# Serial_Expansion.net
KiCad netlist of a schematic drawn in Altium Designer
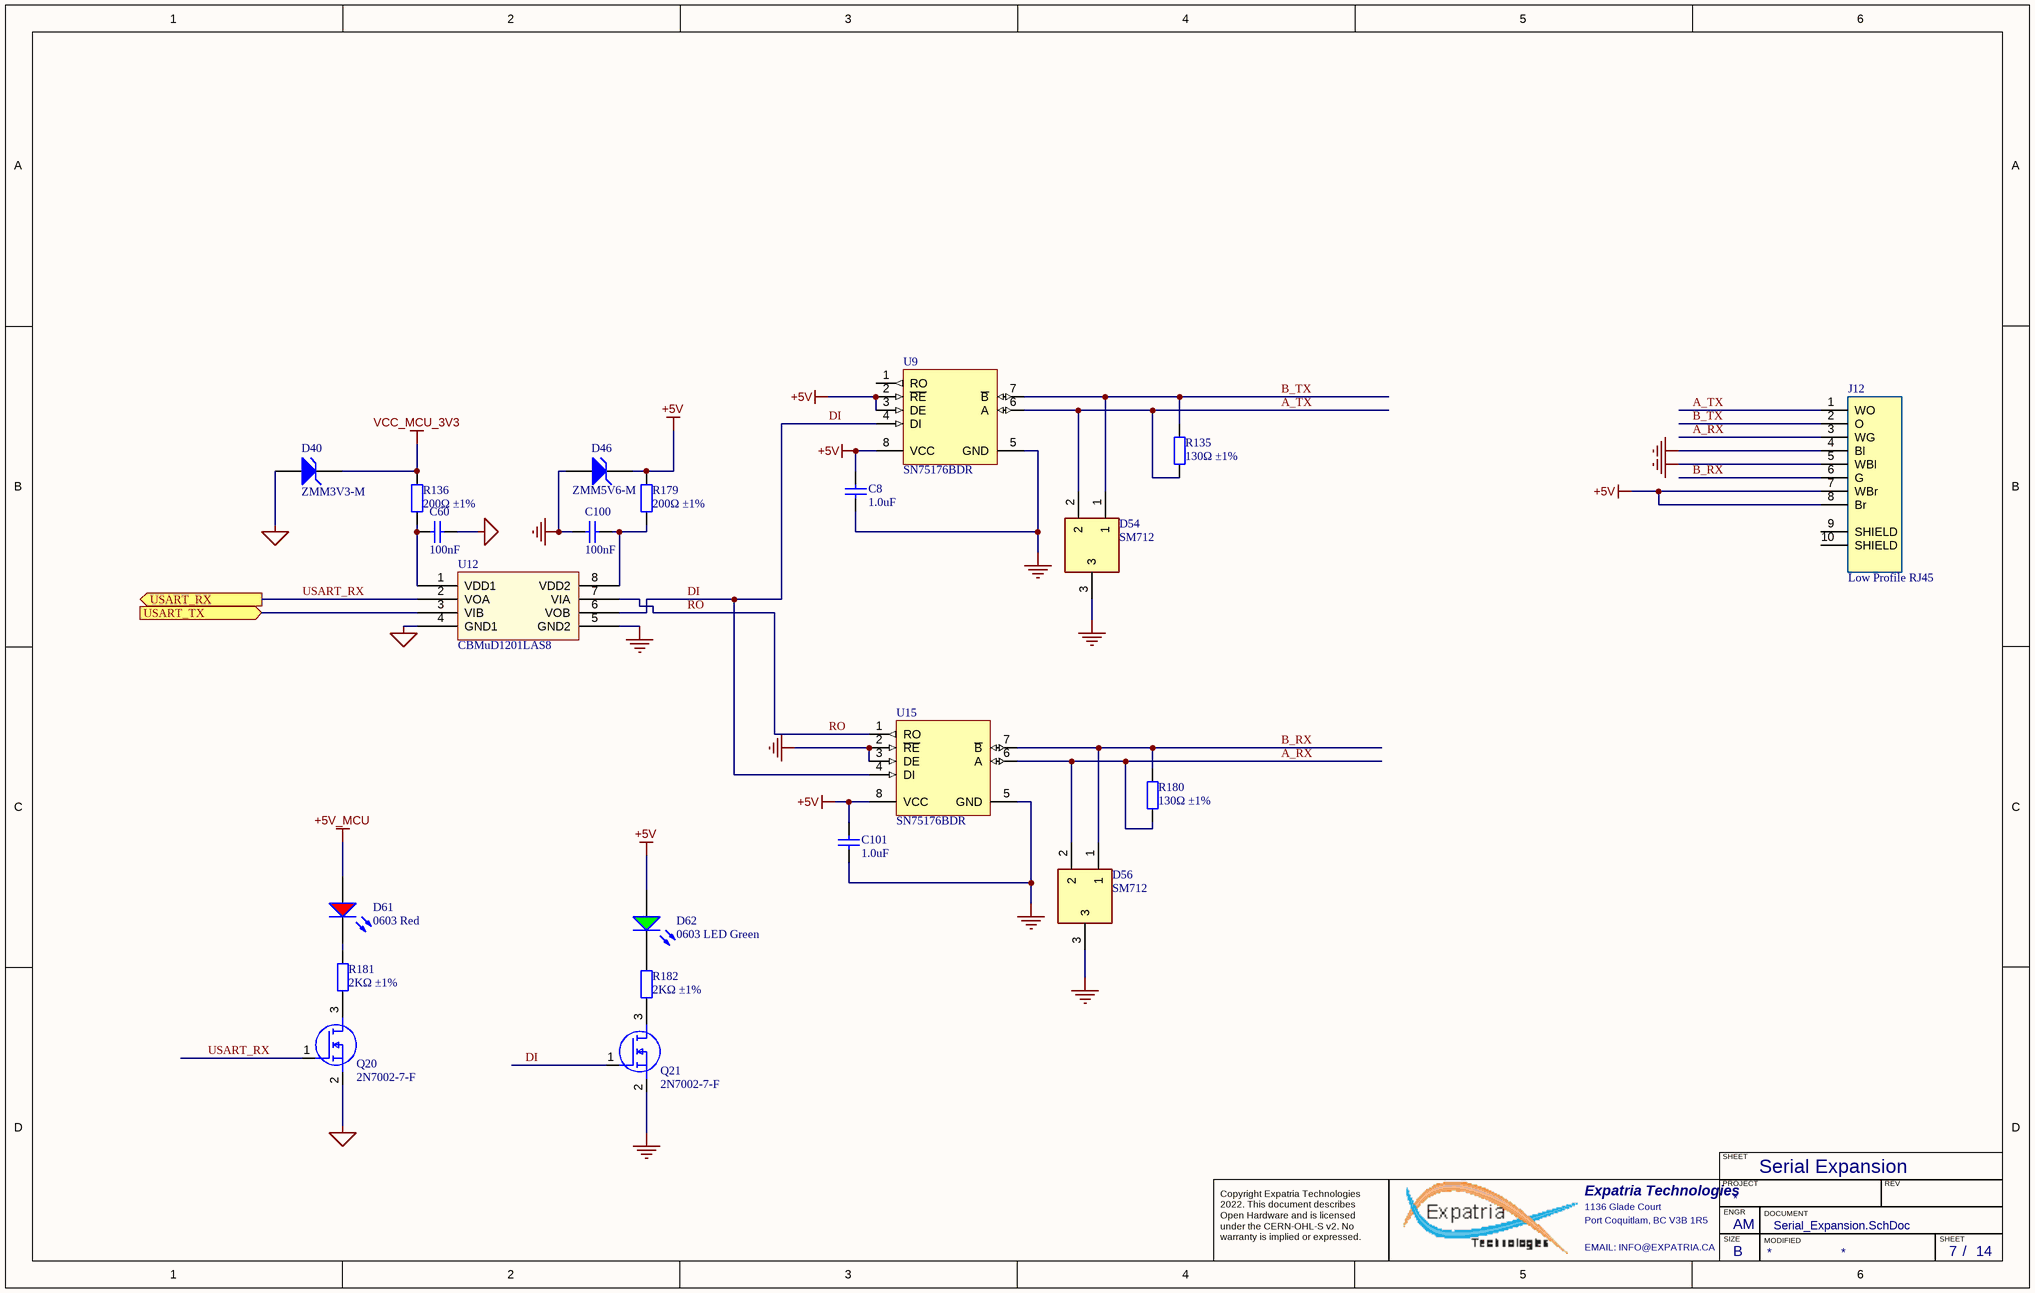
[diagram p0: Serial_Expansion.SchDoc]

(export (version "E")
  (design (tool "Eeschema 10.0.6"))
  (components
    (comp (ref "C8")
      (value "1.0uF")
      (footprint "0402_C")
      (description "Chip capacitor")
      (fields
        (field (name "MANUFACTURER") "Samsung Electro-Mechanics")
        (field (name "PARTNUMBER") "CL05A105KA5NQNC")
      )
      (libsource (lib "Cap") (part "0402 1.0uF (105) 10% 25V"))
    )
    (comp (ref "C60")
      (value "100nF")
      (footprint "0402_C")
      (description "16V 100nF X7R ±10% 0402 Multilayer Ceramic Capacitors MLCC - SMD/SMT ROHS")
      (fields (field (name "MANUFACTURER") "Samsung Electro-Mechanics") (field (name "TOLERANCE") "10%"))
      (libsource (lib "Sienci_Labs") (part "0402 100nF (104) 10% 16V"))
    )
    (comp (ref "C100")
      (value "100nF")
      (footprint "0402_C")
      (description "16V 100nF X7R ±10% 0402 Multilayer Ceramic Capacitors MLCC - SMD/SMT ROHS")
      (fields (field (name "MANUFACTURER") "Samsung Electro-Mechanics") (field (name "TOLERANCE") "10%"))
      (libsource (lib "Sienci_Labs") (part "0402 100nF (104) 10% 16V"))
    )
    (comp (ref "C101")
      (value "1.0uF")
      (footprint "0402_C")
      (description "Chip capacitor")
      (fields
        (field (name "MANUFACTURER") "Samsung Electro-Mechanics")
        (field (name "PARTNUMBER") "CL05A105KA5NQNC")
      )
      (libsource (lib "Cap") (part "0402 1.0uF (105) 10% 25V"))
    )
    (comp (ref "D40")
      (value "ZMM3V3-M")
      (footprint "LL-34")
      (description "Single 3.1V~3.5V 500mW 3.3V LL-34 Zener Diodes ROHS")
      (fields (field (name "MANUFACTURER") "ST(Semtech)"))
      (libsource (lib "Sienci_Labs") (part "LL-34 ZMM3V3-M"))
    )
    (comp (ref "D46")
      (value "ZMM5V6-M")
      (footprint "LL-34")
      (description "Single 5.2V~6V 500mW 5.6V LL-34 Zener Diodes ROHS")
      (fields (field (name "MANUFACTURER") "ST(Semtech)"))
      (libsource (lib "Sienci_Labs") (part "LL-34 ZMM5V6-M"))
    )
    (comp (ref "D54")
      (value "SM712")
      (footprint "SamacSys:SOT95P230X117-3N")
      (description "Bidirectional 12V (Max), 7V (Max) 7.5V / 13.3V 10V / 20V 12A(8/20us) SOT-23-3 TVS RoHS")
      (libsource (lib "*") (part "CDSOT23-SM712"))
    )
    (comp (ref "D56")
      (value "SM712")
      (footprint "SamacSys:SOT95P230X117-3N")
      (description "Bidirectional 12V (Max), 7V (Max) 7.5V / 13.3V 10V / 20V 12A(8/20us) SOT-23-3 TVS RoHS")
      (libsource (lib "*") (part "CDSOT23-SM712"))
    )
    (comp (ref "D61")
      (value "0603 Red")
      (footprint "0603_LED_S1")
      (fields
        (field (name "MANUFACTURER") "Everlight Elec")
        (field (name "MANUFACTURER PART NUMBER") "19-213SURC/S530-A3/TR8")
      )
      (libsource (lib "Sienci_Labs") (part "19-213SURC/S530-A3/TR8"))
    )
    (comp (ref "D62")
      (value "0603 LED Green")
      (footprint "0603_LED_S1")
      (fields
        (field (name "MANUFACTURER PART NUMBER") "19-217/GHC-YR1S2/3T")
        (field (name "MANUFACTURER") "Everlight Elec")
      )
      (libsource (lib "Sienci_Labs") (part "19-217/GHC-YR1S2/3T"))
    )
    (comp (ref "J12")
      (value "Low Profile RJ45")
      (footprint "RJ45-SMD_MJ88-B011-HLSV6-P")
      (description "Micro USB")
      (fields (field (name "MF") "Heling"))
      (libsource (lib "Universal_CNC_Breakout") (part "MJ88-B011-HLSV6-P"))
    )
    (comp (ref "Q20")
      (value "2N7002-7-F")
      (footprint "SOT-23(SOT-23-3)")
      (description "60V 115mA 7.5Ω@5V,50mA 370mW N Channel SOT-23 MOSFETs ROHS")
      (fields (field (name "MANUFACTURER") "Diodes Inc.") (field (name "MOUSER PART NUMBER") "621-2N7002-F"))
      (libsource (lib "Sienci_Labs") (part "2N7002-7-F"))
    )
    (comp (ref "Q21")
      (value "2N7002-7-F")
      (footprint "SOT-23(SOT-23-3)")
      (description "60V 115mA 7.5Ω@5V,50mA 370mW N Channel SOT-23 MOSFETs ROHS")
      (fields (field (name "MANUFACTURER") "Diodes Inc.") (field (name "MOUSER PART NUMBER") "621-2N7002-F"))
      (libsource (lib "Sienci_Labs") (part "2N7002-7-F"))
    )
    (comp (ref "R135")
      (value "130Ω ±1%")
      (footprint "0603_R")
      (description "Chip resistor")
      (fields (field (name "MANUFACTURER") "Uniroyal Elec") (field (name "PARTNUMBER") "0603WAF1300T5E"))
      (libsource (lib "RES") (part "0603 130R (1300) 1%"))
    )
    (comp (ref "R136")
      (value "200Ω ±1%")
      (footprint "0402_R")
      (description "Chip resistor")
      (fields
        (field (name "MANUFACTURER") "Uniroyal Elec")
        (field (name "MANUFACTURER PART NUMBER") "0402WGF2000TCE")
      )
      (libsource (lib "RES") (part "0402 200R (2000) 1%"))
    )
    (comp (ref "R179")
      (value "200Ω ±1%")
      (footprint "0402_R")
      (description "Chip resistor")
      (fields
        (field (name "MANUFACTURER") "Uniroyal Elec")
        (field (name "MANUFACTURER PART NUMBER") "0402WGF2000TCE")
      )
      (libsource (lib "RES") (part "0402 200R (2000) 1%"))
    )
    (comp (ref "R180")
      (value "130Ω ±1%")
      (footprint "0603_R")
      (description "Chip resistor")
      (fields (field (name "MANUFACTURER") "Uniroyal Elec") (field (name "PARTNUMBER") "0603WAF1300T5E"))
      (libsource (lib "RES") (part "0603 130R (1300) 1%"))
    )
    (comp (ref "R181")
      (value "2KΩ ±1%")
      (footprint "0402_R")
      (description "Chip resistor")
      (fields
        (field (name "MANUFACTURER") "Uniroyal Elec")
        (field (name "MANUFACTURER PART NUMBER") "0402WGF2001TCE")
      )
      (libsource (lib "RES") (part "0402 2K (2001) 1%"))
    )
    (comp (ref "R182")
      (value "2KΩ ±1%")
      (footprint "0402_R")
      (description "Chip resistor")
      (fields
        (field (name "MANUFACTURER") "Uniroyal Elec")
        (field (name "MANUFACTURER PART NUMBER") "0402WGF2001TCE")
      )
      (libsource (lib "RES") (part "0402 2K (2001) 1%"))
    )
    (comp (ref "U9")
      (value "SN75176BDR")
      (footprint "Miscellaneous Devices LC:SOIC-8_150mil")
      (description "RS-485/RS-422")
      (libsource (lib "IC") (part "SN75176BDR_[C7063]"))
    )
    (comp (ref "U12")
      (value "CBMuD1201LAS8")
      (footprint "SOIC-8_150mil")
      (description "Dual Channel Isolator")
      (fields (field (name "MANUFACTURER") "Corebai Microelectronics"))
      (libsource (lib "Sienci_Labs") (part "CBMuD1201LAS8"))
    )
    (comp (ref "U15")
      (value "SN75176BDR")
      (footprint "Miscellaneous Devices LC:SOIC-8_150mil")
      (description "RS-485/RS-422")
      (libsource (lib "IC") (part "SN75176BDR_[C7063]"))
    )
  )
  (nets
    (net (code "1") (name "+5V") (class "Default")
      (node (ref "C101") (pin "2") (pinfunction "2_2") (pintype "passive"))
      (node (ref "C8") (pin "2") (pinfunction "2_2") (pintype "passive"))
      (node (ref "D46") (pin "2") (pinfunction "K_2") (pintype "passive"))
      (node (ref "D62") (pin "A") (pinfunction "A_A") (pintype "passive"))
      (node (ref "J12") (pin "7") (pinfunction "WBr_7") (pintype "passive"))
      (node (ref "J12") (pin "8") (pinfunction "Br_8") (pintype "passive"))
      (node (ref "R179") (pin "2") (pinfunction "2_2") (pintype "passive"))
      (node (ref "U15") (pin "8") (pinfunction "VCC_8") (pintype "power_in"))
      (node (ref "U9") (pin "2") (pinfunction "~{RE}_2") (pintype "input"))
      (node (ref "U9") (pin "3") (pinfunction "DE_3") (pintype "input"))
      (node (ref "U9") (pin "8") (pinfunction "VCC_8") (pintype "power_in"))
    )
    (net (code "2") (name "+5V_MCU") (class "Default")
      (node (ref "D61") (pin "A") (pinfunction "A_A") (pintype "passive"))
    )
    (net (code "3") (name "/A_RX") (class "Default")
      (node (ref "D56") (pin "2") (pinfunction "2_2") (pintype "passive"))
      (node (ref "J12") (pin "3") (pinfunction "WG_3") (pintype "passive"))
      (node (ref "R180") (pin "1") (pinfunction "1_1") (pintype "passive"))
      (node (ref "U15") (pin "6") (pinfunction "A_6") (pintype "bidirectional"))
    )
    (net (code "4") (name "/A_TX") (class "Default")
      (node (ref "D54") (pin "2") (pinfunction "2_2") (pintype "passive"))
      (node (ref "J12") (pin "1") (pinfunction "WO_1") (pintype "passive"))
      (node (ref "R135") (pin "1") (pinfunction "1_1") (pintype "passive"))
      (node (ref "U9") (pin "6") (pinfunction "A_6") (pintype "bidirectional"))
    )
    (net (code "5") (name "/B_RX") (class "Default")
      (node (ref "D56") (pin "1") (pinfunction "1_1") (pintype "passive"))
      (node (ref "J12") (pin "6") (pinfunction "G_6") (pintype "passive"))
      (node (ref "R180") (pin "2") (pinfunction "2_2") (pintype "passive"))
      (node (ref "U15") (pin "7") (pinfunction "~{B}_7") (pintype "bidirectional"))
    )
    (net (code "6") (name "/B_TX") (class "Default")
      (node (ref "D54") (pin "1") (pinfunction "1_1") (pintype "passive"))
      (node (ref "J12") (pin "2") (pinfunction "O_2") (pintype "passive"))
      (node (ref "R135") (pin "2") (pinfunction "2_2") (pintype "passive"))
      (node (ref "U9") (pin "7") (pinfunction "~{B}_7") (pintype "bidirectional"))
    )
    (net (code "7") (name "/DI") (class "Default")
      (node (ref "Q21") (pin "1") (pinfunction "G_1") (pintype "passive"))
      (node (ref "U12") (pin "6") (pinfunction "VOB_6") (pintype "passive"))
      (node (ref "U15") (pin "4") (pinfunction "DI_4") (pintype "input"))
      (node (ref "U9") (pin "4") (pinfunction "DI_4") (pintype "input"))
    )
    (net (code "8") (name "/RO") (class "Default")
      (node (ref "U12") (pin "7") (pinfunction "VIA_7") (pintype "passive"))
      (node (ref "U15") (pin "1") (pinfunction "RO_1") (pintype "output"))
    )
    (net (code "9") (name "/USART_RX") (class "Default")
      (node (ref "Q20") (pin "1") (pinfunction "G_1") (pintype "passive"))
      (node (ref "U12") (pin "2") (pinfunction "VOA_2") (pintype "passive"))
    )
    (net (code "10") (name "/USART_TX") (class "Default")
      (node (ref "U12") (pin "3") (pinfunction "VIB_3") (pintype "passive"))
    )
    (net (code "11") (name "GND") (class "Default")
      (node (ref "C100") (pin "1") (pinfunction "1_1") (pintype "passive"))
      (node (ref "C101") (pin "1") (pinfunction "1_1") (pintype "passive"))
      (node (ref "C8") (pin "1") (pinfunction "1_1") (pintype "passive"))
      (node (ref "D46") (pin "1") (pinfunction "A_1") (pintype "passive"))
      (node (ref "D54") (pin "3") (pinfunction "3_3") (pintype "passive"))
      (node (ref "D56") (pin "3") (pinfunction "3_3") (pintype "passive"))
      (node (ref "J12") (pin "4") (pinfunction "Bl_4") (pintype "passive"))
      (node (ref "J12") (pin "5") (pinfunction "WBl_5") (pintype "passive"))
      (node (ref "Q21") (pin "2") (pinfunction "S_2") (pintype "passive"))
      (node (ref "U12") (pin "5") (pinfunction "GND2_5") (pintype "passive"))
      (node (ref "U15") (pin "2") (pinfunction "~{RE}_2") (pintype "input"))
      (node (ref "U15") (pin "3") (pinfunction "DE_3") (pintype "input"))
      (node (ref "U15") (pin "5") (pinfunction "GND_5") (pintype "power_in"))
      (node (ref "U9") (pin "5") (pinfunction "GND_5") (pintype "power_in"))
    )
    (net (code "12") (name "MCU_GND") (class "Default")
      (node (ref "C60") (pin "2") (pinfunction "2_2") (pintype "passive"))
      (node (ref "D40") (pin "1") (pinfunction "A_1") (pintype "passive"))
      (node (ref "Q20") (pin "2") (pinfunction "S_2") (pintype "passive"))
      (node (ref "U12") (pin "4") (pinfunction "GND1_4") (pintype "passive"))
    )
    (net (code "13") (name "Net-(D61-PadK)") (class "Default")
      (node (ref "D61") (pin "K") (pinfunction "K_K") (pintype "passive"))
      (node (ref "R181") (pin "2") (pinfunction "2_2") (pintype "passive"))
    )
    (net (code "14") (name "Net-(D62-PadK)") (class "Default")
      (node (ref "D62") (pin "K") (pinfunction "K_K") (pintype "passive"))
      (node (ref "R182") (pin "2") (pinfunction "2_2") (pintype "passive"))
    )
    (net (code "15") (name "Net-(Q20-D)") (class "Default")
      (node (ref "Q20") (pin "3") (pinfunction "D_3") (pintype "passive"))
      (node (ref "R181") (pin "1") (pinfunction "1_1") (pintype "passive"))
    )
    (net (code "16") (name "Net-(Q21-D)") (class "Default")
      (node (ref "Q21") (pin "3") (pinfunction "D_3") (pintype "passive"))
      (node (ref "R182") (pin "1") (pinfunction "1_1") (pintype "passive"))
    )
    (net (code "17") (name "Net-(U12-VDD1)") (class "Default")
      (node (ref "C60") (pin "1") (pinfunction "1_1") (pintype "passive"))
      (node (ref "R136") (pin "1") (pinfunction "1_1") (pintype "passive"))
      (node (ref "U12") (pin "1") (pinfunction "VDD1_1") (pintype "passive"))
    )
    (net (code "18") (name "Net-(U12-VDD2)") (class "Default")
      (node (ref "C100") (pin "2") (pinfunction "2_2") (pintype "passive"))
      (node (ref "R179") (pin "1") (pinfunction "1_1") (pintype "passive"))
      (node (ref "U12") (pin "8") (pinfunction "VDD2_8") (pintype "passive"))
    )
    (net (code "19") (name "VCC_MCU_3V3") (class "Default")
      (node (ref "D40") (pin "2") (pinfunction "K_2") (pintype "passive"))
      (node (ref "R136") (pin "2") (pinfunction "2_2") (pintype "passive"))
    )
    (net (code "20") (name "unconnected-(J12-SHIELD-Pad9)") (class "Default")
      (node (ref "J12") (pin "9") (pinfunction "SHIELD_9") (pintype "passive"))
    )
    (net (code "21") (name "unconnected-(J12-SHIELD-Pad10)") (class "Default")
      (node (ref "J12") (pin "10") (pinfunction "SHIELD_10") (pintype "passive"))
    )
    (net (code "22") (name "unconnected-(U9-RO-Pad1)") (class "Default")
      (node (ref "U9") (pin "1") (pinfunction "RO_1") (pintype "output"))
    )
  )
)
